# CH32V467VET-USB.net
KiCad netlist of a schematic drawn in Altium Designer
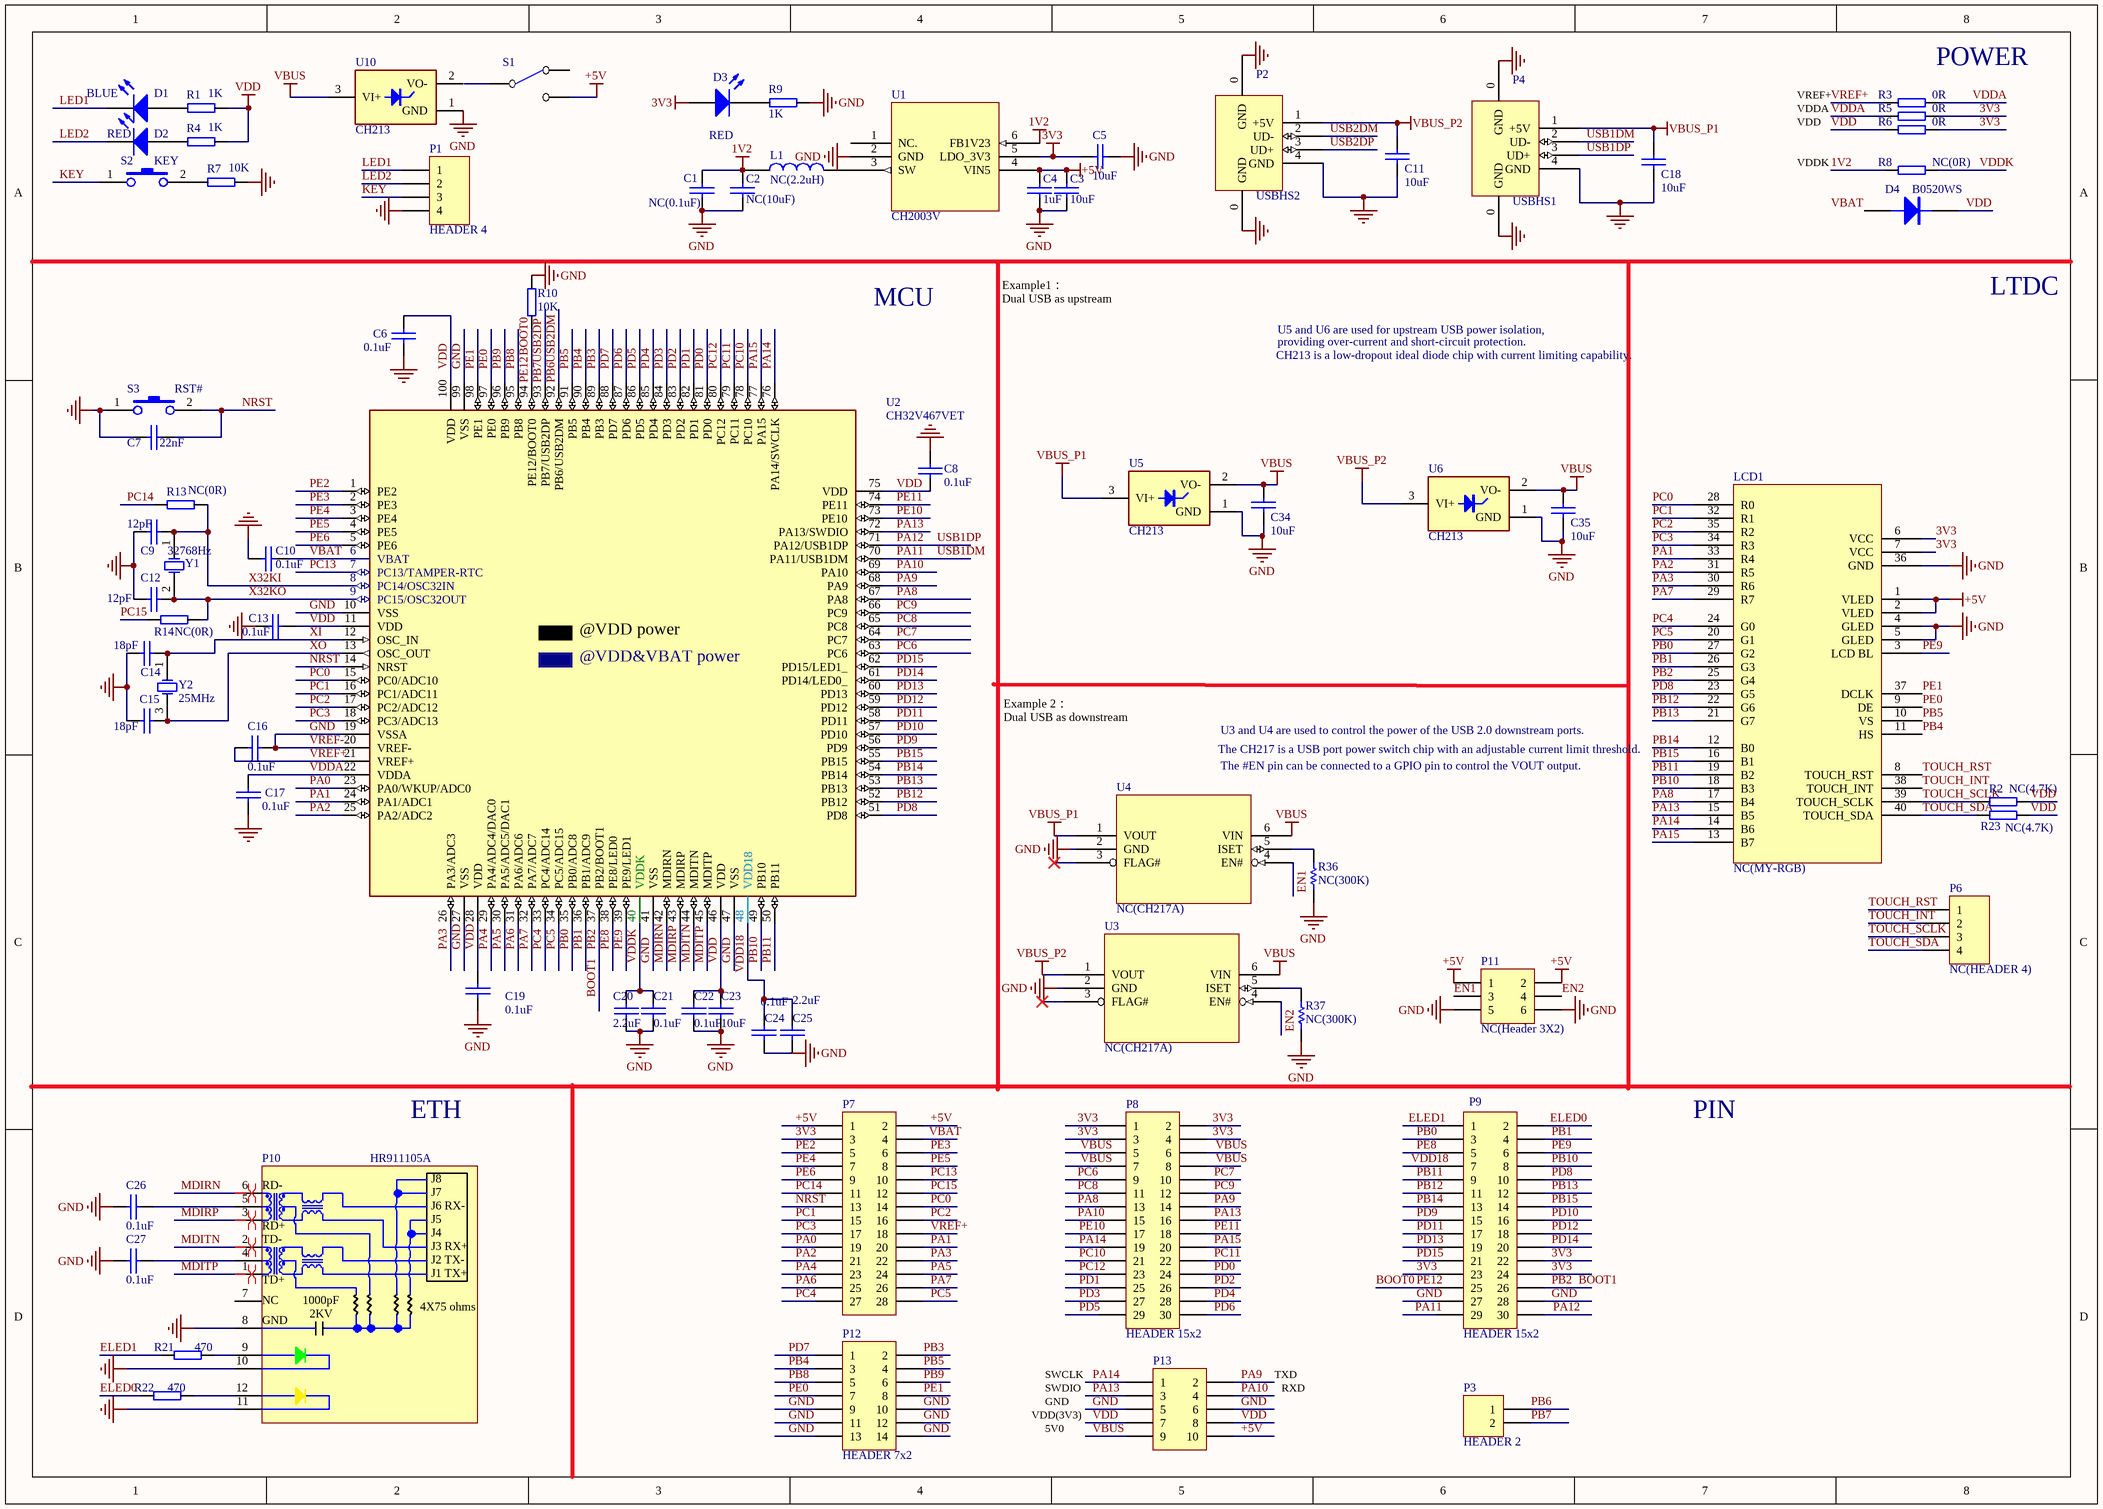
[diagram p0: CH32V467VET-USB.SchDoc]

(export (version "E")
  (design (tool "Eeschema 10.0.6"))
  (components
    (comp (ref "C1")
      (value "NC(0.1uF)")
      (footprint "0402_C")
      (description "Capacitor")
      (libsource (lib "") (part "CAP_2"))
    )
    (comp (ref "C2")
      (value "NC(10uF)")
      (footprint "0603_C")
      (description "Capacitor")
      (libsource (lib "*") (part "CAP"))
    )
    (comp (ref "C3")
      (value "10uF")
      (footprint "0603_C")
      (description "Capacitor")
      (libsource (lib "*") (part "CAP"))
    )
    (comp (ref "C4")
      (value "1uF")
      (footprint "0402_C")
      (description "Capacitor")
      (libsource (lib "") (part "CAP_2"))
    )
    (comp (ref "C5")
      (value "10uF")
      (footprint "0603_C")
      (description "Capacitor")
      (libsource (lib "*") (part "CAP"))
    )
    (comp (ref "C6")
      (value "0.1uF")
      (footprint "0402_C")
      (description "Capacitor")
      (libsource (lib "*") (part "CAP"))
    )
    (comp (ref "C7")
      (value "22nF")
      (footprint "0402_C")
      (description "Capacitor")
      (libsource (lib "") (part "CAP_1"))
    )
    (comp (ref "C8")
      (value "0.1uF")
      (footprint "0402_C")
      (description "Capacitor")
      (libsource (lib "*") (part "CAP"))
    )
    (comp (ref "C9")
      (value "12pF")
      (footprint "0402_C")
      (description "Capacitor")
      (libsource (lib "*") (part "CAP"))
    )
    (comp (ref "C10")
      (value "0.1uF")
      (footprint "0402_C")
      (description "Capacitor")
      (libsource (lib "*") (part "CAP"))
    )
    (comp (ref "C11")
      (value "10uF")
      (footprint "0603_C")
      (description "Capacitor")
      (libsource (lib "") (part "CAP_1"))
    )
    (comp (ref "C12")
      (value "12pF")
      (footprint "0402_C")
      (description "Capacitor")
      (libsource (lib "*") (part "CAP"))
    )
    (comp (ref "C13")
      (value "0.1uF")
      (footprint "0402_C")
      (description "Capacitor")
      (libsource (lib "*") (part "CAP"))
    )
    (comp (ref "C14")
      (value "18pF")
      (footprint "0402_C")
      (description "Capacitor")
      (libsource (lib "*") (part "CAP"))
    )
    (comp (ref "C15")
      (value "18pF")
      (footprint "0402_C")
      (description "Capacitor")
      (libsource (lib "*") (part "CAP"))
    )
    (comp (ref "C16")
      (value "0.1uF")
      (footprint "0402_C")
      (description "Capacitor")
      (libsource (lib "*") (part "CAP"))
    )
    (comp (ref "C17")
      (value "0.1uF")
      (footprint "0402_C")
      (description "Capacitor")
      (libsource (lib "*") (part "CAP"))
    )
    (comp (ref "C18")
      (value "10uF")
      (footprint "0603_C")
      (description "Capacitor")
      (libsource (lib "") (part "CAP_1"))
    )
    (comp (ref "C19")
      (value "0.1uF")
      (footprint "0402_C")
      (description "Capacitor")
      (libsource (lib "*") (part "CAP"))
    )
    (comp (ref "C20")
      (value "2.2uF")
      (footprint "0402_C")
      (description "Capacitor")
      (libsource (lib "*") (part "CAP"))
    )
    (comp (ref "C21")
      (value "0.1uF")
      (footprint "0402_C")
      (description "Capacitor")
      (libsource (lib "*") (part "CAP"))
    )
    (comp (ref "C22")
      (value "0.1uF")
      (footprint "0402_C")
      (description "Capacitor")
      (libsource (lib "*") (part "CAP"))
    )
    (comp (ref "C23")
      (value "10uF")
      (footprint "0402_C")
      (description "Capacitor")
      (libsource (lib "*") (part "CAP"))
    )
    (comp (ref "C24")
      (value "0.1uF")
      (footprint "0402_C")
      (description "Capacitor")
      (libsource (lib "*") (part "CAP"))
    )
    (comp (ref "C25")
      (value "2.2uF")
      (footprint "0402_C")
      (description "Capacitor")
      (libsource (lib "*") (part "CAP"))
    )
    (comp (ref "C26")
      (value "0.1uF")
      (footprint "0402_C")
      (description "Capacitor")
      (libsource (lib "wch_sch_others") (part "CAP"))
    )
    (comp (ref "C27")
      (value "0.1uF")
      (footprint "0402_C")
      (description "Capacitor")
      (libsource (lib "wch_sch_others") (part "CAP"))
    )
    (comp (ref "C34")
      (value "10uF")
      (footprint "0603_C")
      (description "Capacitor")
      (libsource (lib "") (part "CAP_1"))
    )
    (comp (ref "C35")
      (value "10uF")
      (footprint "0603_C")
      (description "Capacitor")
      (libsource (lib "") (part "CAP_1"))
    )
    (comp (ref "D1")
      (value "BLUE")
      (footprint "0603+")
      (description "Typical INFRARED GaAs LED")
      (fields (field (name "PUBLISHER") "Altium Limited"))
      (libsource (lib "*") (part "LED0"))
    )
    (comp (ref "D2")
      (value "RED")
      (footprint "0603+")
      (description "Typical INFRARED GaAs LED")
      (fields (field (name "PUBLISHER") "Altium Limited"))
      (libsource (lib "*") (part "LED0"))
    )
    (comp (ref "D3")
      (value "RED")
      (footprint "0603+")
      (description "Typical INFRARED GaAs LED")
      (fields (field (name "PUBLISHER") "Altium Limited"))
      (libsource (lib "*") (part "LED0"))
    )
    (comp (ref "D4")
      (value "B0520WS")
      (footprint "SOD-323")
      (description "Diode")
      (libsource (lib "*") (part "DIODE"))
    )
    (comp (ref "L1") (value "NC(2.2uH)") (footprint "CD32") (libsource (lib "*") (part "INDUCTOR")))
    (comp (ref "LCD1")
      (value "NC(MY-RGB)")
      (footprint "FPC40P-0.5-FK750M3")
      (libsource (lib "MY-显示") (part "MY-RGB"))
    )
    (comp (ref "P1")
      (value "HEADER 4")
      (footprint "SIP4-2.54mm")
      (description "Header, 4-Pin")
      (libsource (lib "wch_sch_others") (part "HEADER 4"))
    )
    (comp (ref "P2")
      (value "USBHS2")
      (footprint "USBAF")
      (description "USB Port")
      (libsource (lib "*") (part "USB"))
    )
    (comp (ref "P3")
      (value "HEADER 2")
      (footprint "MYPCB:SIP2-2.54mm")
      (description "Header, 2-Pin")
      (libsource (lib "wch_sch_others") (part "HEADER 2"))
    )
    (comp (ref "P4")
      (value "USBHS1")
      (footprint "USBAF")
      (description "USB Port")
      (libsource (lib "*") (part "USB"))
    )
    (comp (ref "P6")
      (value "NC(HEADER 4)")
      (footprint "SIP4-2.54mm")
      (description "Header, 4-Pin")
      (libsource (lib "wch_sch_others") (part "HEADER 4"))
    )
    (comp (ref "P7")
      (value "HEADER 14x2")
      (footprint "MYPCB:IDC28-2.54MM")
      (description "Header, 14-Pin, Dual row")
      (libsource (lib "wch_sch_others") (part "HEADER 14x2"))
    )
    (comp (ref "P8")
      (value "HEADER 15x2")
      (footprint "MYPCB:IDC30-2.54MM")
      (description "Header, 15-Pin, Dual row")
      (libsource (lib "wch_sch_others") (part "HEADER 15x2"))
    )
    (comp (ref "P9")
      (value "HEADER 15x2")
      (footprint "MYPCB:IDC30-2.54MM")
      (description "Header, 15-Pin, Dual row")
      (libsource (lib "wch_sch_others") (part "HEADER 15x2"))
    )
    (comp (ref "P10") (value "HR911105A") (footprint "HR911105A") (libsource (lib "*") (part "HR911105A")))
    (comp (ref "P11")
      (value "NC(Header 3X2)")
      (footprint "HDR2X3")
      (description "Header, 3-Pin, Dual row")
      (fields (field (name "PUBLISHER") "Altium Limited"))
      (libsource (lib "Miscellaneous Connectors") (part "Header 3X2"))
    )
    (comp (ref "P12")
      (value "HEADER 7x2")
      (footprint "MYPCB:IDC14-2.54mm")
      (description "Header, 7-Pin, Dual row")
      (libsource (lib "wch_sch_others") (part "HEADER 7x2"))
    )
    (comp (ref "P13")
      (value "LINK")
      (footprint "IDC10-2.54mm")
      (description "Header, 5-Pin, Dual row, Right Angle")
      (fields (field (name "PUBLISHER") "Altium Limited"))
      (libsource (lib "Miscellaneous Connectors") (part "Header 5X2H"))
    )
    (comp (ref "R1") (value "1K") (footprint "0402") (libsource (lib "wch_sch_others") (part "RES")))
    (comp (ref "R2") (value "NC(4.7K)") (footprint "0402") (libsource (lib "wch_sch_others") (part "RES")))
    (comp (ref "R3") (value "0R") (footprint "0402") (libsource (lib "*") (part "R")))
    (comp (ref "R4") (value "1K") (footprint "0402") (libsource (lib "wch_sch_others") (part "RES")))
    (comp (ref "R5") (value "0R") (footprint "0402") (libsource (lib "*") (part "R")))
    (comp (ref "R6") (value "0R") (footprint "0402") (libsource (lib "*") (part "R")))
    (comp (ref "R7") (value "10K") (footprint "0402") (libsource (lib "wch_sch_others") (part "RES")))
    (comp (ref "R8") (value "NC(0R)") (footprint "0402") (libsource (lib "*") (part "R")))
    (comp (ref "R9") (value "1K") (footprint "0402") (libsource (lib "wch_sch_others") (part "RES")))
    (comp (ref "R10") (value "10K") (footprint "0402") (libsource (lib "wch_sch_others") (part "RES")))
    (comp (ref "R13") (value "NC(0R)") (footprint "0402") (libsource (lib "wch_sch_others") (part "RES")))
    (comp (ref "R14") (value "NC(0R)") (footprint "0402") (libsource (lib "wch_sch_others") (part "RES")))
    (comp (ref "R21") (value "470") (footprint "0402") (libsource (lib "wch_sch_others") (part "RES")))
    (comp (ref "R22") (value "470") (footprint "0402") (libsource (lib "wch_sch_others") (part "RES")))
    (comp (ref "R23") (value "NC(4.7K)") (footprint "0402") (libsource (lib "wch_sch_others") (part "RES")))
    (comp (ref "R36")
      (value "NC(300K)")
      (footprint "0603")
      (description "Resistor")
      (fields (field (name "PUBLISHER") "Altium Limited"))
      (libsource (lib "MYLIB") (part "0603-1"))
    )
    (comp (ref "R37")
      (value "NC(300K)")
      (footprint "0603")
      (description "Resistor")
      (fields (field (name "PUBLISHER") "Altium Limited"))
      (libsource (lib "MYLIB") (part "0603-1"))
    )
    (comp (ref "S1") (value "SW SPDT") (footprint "SW1") (libsource (lib "*") (part "SW SPDT")))
    (comp (ref "S2")
      (value "KEY")
      (footprint "SMD_6.1x3.65x2.5mm-KEY")
      (libsource (lib "wch_sch_others") (part "KEY1"))
    )
    (comp (ref "S3")
      (value "RST#")
      (footprint "SMD_6.1x3.65x2.5mm-KEY")
      (libsource (lib "wch_sch_others") (part "KEY1"))
    )
    (comp (ref "U1")
      (value "CH2003V")
      (footprint "SOT-23-6")
      (description "Step-Down DC-DC Converter, 5V input, 1.23V * 800mA output, with LDO 3.3V * 200mA")
      (libsource (lib "CHXXX") (part "CH2003V"))
    )
    (comp (ref "U2")
      (value "CH32V467VET")
      (footprint "LQFP100")
      (description "RISC-V FPU HD-MCU, 175MHz, USB_480M, 100M Ethernet & Phy, CAN, DVP, ADC, DAC, SRAM")
      (libsource (lib "CHXXX") (part "CH32V467VET"))
    )
    (comp (ref "U3")
      (value "NC(CH217A)")
      (footprint "SOT-23-6")
      (description "Current-Limited USB Power Distribution Switch")
      (libsource (lib "CHXXX") (part "CH217K"))
    )
    (comp (ref "U4")
      (value "NC(CH217A)")
      (footprint "SOT-23-6")
      (description "Current-Limited USB Power Distribution Switch")
      (libsource (lib "CHXXX") (part "CH217K"))
    )
    (comp (ref "U5")
      (value "CH213")
      (footprint "SOT-23-3")
      (description "Ideal Diode 5V*1A")
      (libsource (lib "CHXXX") (part "CH213E"))
    )
    (comp (ref "U6")
      (value "CH213")
      (footprint "SOT-23-3")
      (description "Ideal Diode 5V*1A")
      (libsource (lib "CHXXX") (part "CH213E"))
    )
    (comp (ref "U10")
      (value "CH213")
      (footprint "SOT-23-3")
      (description "Ideal Diode 5V*1A")
      (libsource (lib "CHXXX") (part "CH213E"))
    )
    (comp (ref "Y1")
      (value "32768Hz")
      (footprint "FC-135")
      (description "Crystal Oscillator")
      (fields (field (name "PUBLISHER") "Altium Limited"))
      (libsource (lib "") (part "XTAL_1"))
    )
    (comp (ref "Y2")
      (value "25MHz")
      (footprint "XT3225")
      (description "Crystal Oscillator")
      (fields (field (name "PUBLISHER") "Altium Limited"))
      (libsource (lib "*") (part "XTAL"))
    )
  )
  (nets
    (net (code "1") (name "+5V") (class "Default")
      (node (ref "C3") (pin "2") (pinfunction "2_2") (pintype "passive"))
      (node (ref "C4") (pin "2") (pinfunction "2_2") (pintype "passive"))
      (node (ref "LCD1") (pin "1") (pinfunction "VLED_1") (pintype "passive"))
      (node (ref "LCD1") (pin "2") (pinfunction "VLED_2") (pintype "passive"))
      (node (ref "P11") (pin "1") (pinfunction "1_1") (pintype "passive"))
      (node (ref "P11") (pin "2") (pinfunction "2_2") (pintype "passive"))
      (node (ref "P13") (pin "10") (pinfunction "10_10") (pintype "passive"))
      (node (ref "P7") (pin "1") (pinfunction "1_1") (pintype "passive"))
      (node (ref "P7") (pin "2") (pinfunction "2_2") (pintype "passive"))
      (node (ref "S1") (pin "2") (pinfunction "NC_2") (pintype "passive"))
      (node (ref "U1") (pin "4") (pinfunction "VIN5_4") (pintype "power_in"))
    )
    (net (code "3") (name "/BOOT0") (class "Default")
      (node (ref "P9") (pin "25") (pinfunction "25_25") (pintype "passive"))
      (node (ref "R10") (pin "2") (pintype "passive"))
      (node (ref "U2") (pin "94") (pinfunction "PE12/BOOT0_94") (pintype "bidirectional"))
    )
    (net (code "4") (name "/BOOT1") (class "Default")
      (node (ref "LCD1") (pin "25") (pinfunction "G4_25") (pintype "passive"))
      (node (ref "P9") (pin "26") (pinfunction "26_26") (pintype "passive"))
      (node (ref "U2") (pin "37") (pinfunction "PB2/BOOT1_37") (pintype "bidirectional"))
    )
    (net (code "5") (name "/ELED0") (class "Default")
      (node (ref "P9") (pin "2") (pinfunction "2_2") (pintype "passive"))
      (node (ref "R22") (pin "1") (pintype "passive"))
    )
    (net (code "6") (name "/ELED1") (class "Default")
      (node (ref "P9") (pin "1") (pinfunction "1_1") (pintype "passive"))
      (node (ref "R21") (pin "1") (pintype "passive"))
    )
    (net (code "7") (name "/EN1") (class "Default")
      (node (ref "P11") (pin "3") (pinfunction "3_3") (pintype "passive"))
      (node (ref "U4") (pin "4") (pinfunction "EN#_4") (pintype "input"))
    )
    (net (code "8") (name "/EN2") (class "Default")
      (node (ref "P11") (pin "4") (pinfunction "4_4") (pintype "passive"))
      (node (ref "U3") (pin "4") (pinfunction "EN#_4") (pintype "input"))
    )
    (net (code "9") (name "/KEY") (class "Default")
      (node (ref "P1") (pin "3") (pinfunction "3_3") (pintype "passive"))
      (node (ref "S2") (pin "1") (pinfunction "1_1") (pintype "passive"))
    )
    (net (code "10") (name "/LED1") (class "Default")
      (node (ref "D1") (pin "2") (pinfunction "K_2") (pintype "passive"))
      (node (ref "P1") (pin "1") (pinfunction "1_1") (pintype "passive"))
    )
    (net (code "11") (name "/LED2") (class "Default")
      (node (ref "D2") (pin "2") (pinfunction "K_2") (pintype "passive"))
      (node (ref "P1") (pin "2") (pinfunction "2_2") (pintype "passive"))
    )
    (net (code "12") (name "/MDIRN") (class "Default")
      (node (ref "P10") (pin "6") (pintype "passive"))
      (node (ref "U2") (pin "42") (pinfunction "MDIRN_42") (pintype "bidirectional"))
    )
    (net (code "13") (name "/MDIRP") (class "Default")
      (node (ref "P10") (pin "3") (pintype "passive"))
      (node (ref "U2") (pin "43") (pinfunction "MDIRP_43") (pintype "bidirectional"))
    )
    (net (code "14") (name "/MDITN") (class "Default")
      (node (ref "P10") (pin "2") (pintype "passive"))
      (node (ref "U2") (pin "44") (pinfunction "MDITN_44") (pintype "bidirectional"))
    )
    (net (code "15") (name "/MDITP") (class "Default")
      (node (ref "P10") (pin "1") (pintype "passive"))
      (node (ref "U2") (pin "45") (pinfunction "MDITP_45") (pintype "bidirectional"))
    )
    (net (code "16") (name "/NRST") (class "Default")
      (node (ref "C7") (pin "2") (pinfunction "2_2") (pintype "passive"))
      (node (ref "P7") (pin "13") (pinfunction "13_13") (pintype "passive"))
      (node (ref "S3") (pin "2") (pinfunction "2_2") (pintype "passive"))
      (node (ref "U2") (pin "14") (pinfunction "NRST_14") (pintype "input"))
    )
    (net (code "17") (name "/PA0") (class "Default")
      (node (ref "P7") (pin "19") (pinfunction "19_19") (pintype "passive"))
      (node (ref "U2") (pin "23") (pinfunction "PA0/WKUP/ADC0_23") (pintype "bidirectional"))
    )
    (net (code "18") (name "/PA1") (class "Default")
      (node (ref "LCD1") (pin "33") (pinfunction "R4_33") (pintype "passive"))
      (node (ref "P7") (pin "20") (pinfunction "20_20") (pintype "passive"))
      (node (ref "U2") (pin "24") (pinfunction "PA1/ADC1_24") (pintype "bidirectional"))
    )
    (net (code "19") (name "/PA2") (class "Default")
      (node (ref "LCD1") (pin "31") (pinfunction "R5_31") (pintype "passive"))
      (node (ref "P7") (pin "21") (pinfunction "21_21") (pintype "passive"))
      (node (ref "U2") (pin "25") (pinfunction "PA2/ADC2_25") (pintype "bidirectional"))
    )
    (net (code "20") (name "/PA3") (class "Default")
      (node (ref "LCD1") (pin "30") (pinfunction "R6_30") (pintype "passive"))
      (node (ref "P7") (pin "22") (pinfunction "22_22") (pintype "passive"))
      (node (ref "U2") (pin "26") (pinfunction "PA3/ADC3_26") (pintype "bidirectional"))
    )
    (net (code "21") (name "/PA4") (class "Default")
      (node (ref "P7") (pin "23") (pinfunction "23_23") (pintype "passive"))
      (node (ref "U2") (pin "29") (pinfunction "PA4/ADC4/DAC0_29") (pintype "bidirectional"))
    )
    (net (code "22") (name "/PA5") (class "Default")
      (node (ref "P7") (pin "24") (pinfunction "24_24") (pintype "passive"))
      (node (ref "U2") (pin "30") (pinfunction "PA5/ADC5/DAC1_30") (pintype "bidirectional"))
    )
    (net (code "23") (name "/PA6") (class "Default")
      (node (ref "P7") (pin "25") (pinfunction "25_25") (pintype "passive"))
      (node (ref "U2") (pin "31") (pinfunction "PA6/ADC6_31") (pintype "bidirectional"))
    )
    (net (code "24") (name "/PA7") (class "Default")
      (node (ref "LCD1") (pin "29") (pinfunction "R7_29") (pintype "passive"))
      (node (ref "P7") (pin "26") (pinfunction "26_26") (pintype "passive"))
      (node (ref "U2") (pin "32") (pinfunction "PA7/ADC7_32") (pintype "bidirectional"))
    )
    (net (code "25") (name "/PA8") (class "Default")
      (node (ref "LCD1") (pin "17") (pinfunction "B4_17") (pintype "passive"))
      (node (ref "P8") (pin "13") (pinfunction "13_13") (pintype "passive"))
      (node (ref "U2") (pin "67") (pinfunction "PA8_67") (pintype "bidirectional"))
    )
    (net (code "26") (name "/PA9") (class "Default")
      (node (ref "P13") (pin "2") (pinfunction "2_2") (pintype "passive"))
      (node (ref "P8") (pin "14") (pinfunction "14_14") (pintype "passive"))
      (node (ref "U2") (pin "68") (pinfunction "PA9_68") (pintype "bidirectional"))
    )
    (net (code "27") (name "/PA10") (class "Default")
      (node (ref "P13") (pin "4") (pinfunction "4_4") (pintype "passive"))
      (node (ref "P8") (pin "15") (pinfunction "15_15") (pintype "passive"))
      (node (ref "U2") (pin "69") (pinfunction "PA10_69") (pintype "bidirectional"))
    )
    (net (code "28") (name "/PA11") (class "Default")
      (node (ref "P4") (pin "2") (pinfunction "UD-_2") (pintype "bidirectional"))
      (node (ref "P9") (pin "29") (pinfunction "29_29") (pintype "passive"))
      (node (ref "U2") (pin "70") (pinfunction "PA11/USB1DM_70") (pintype "bidirectional"))
    )
    (net (code "29") (name "/PA12") (class "Default")
      (node (ref "P4") (pin "3") (pinfunction "UD+_3") (pintype "bidirectional"))
      (node (ref "P9") (pin "30") (pinfunction "30_30") (pintype "passive"))
      (node (ref "U2") (pin "71") (pinfunction "PA12/USB1DP_71") (pintype "bidirectional"))
    )
    (net (code "30") (name "/PA13") (class "Default")
      (node (ref "LCD1") (pin "15") (pinfunction "B5_15") (pintype "passive"))
      (node (ref "P13") (pin "3") (pinfunction "3_3") (pintype "passive"))
      (node (ref "P8") (pin "16") (pinfunction "16_16") (pintype "passive"))
      (node (ref "U2") (pin "72") (pinfunction "PA13/SWDIO_72") (pintype "bidirectional"))
    )
    (net (code "31") (name "/PA14") (class "Default")
      (node (ref "LCD1") (pin "14") (pinfunction "B6_14") (pintype "passive"))
      (node (ref "P13") (pin "1") (pinfunction "1_1") (pintype "passive"))
      (node (ref "P8") (pin "19") (pinfunction "19_19") (pintype "passive"))
      (node (ref "U2") (pin "76") (pinfunction "PA14/SWCLK_76") (pintype "bidirectional"))
    )
    (net (code "32") (name "/PA15") (class "Default")
      (node (ref "LCD1") (pin "13") (pinfunction "B7_13") (pintype "passive"))
      (node (ref "P8") (pin "20") (pinfunction "20_20") (pintype "passive"))
      (node (ref "U2") (pin "77") (pinfunction "PA15_77") (pintype "bidirectional"))
    )
    (net (code "33") (name "/PB0") (class "Default")
      (node (ref "LCD1") (pin "27") (pinfunction "G2_27") (pintype "passive"))
      (node (ref "P9") (pin "3") (pinfunction "3_3") (pintype "passive"))
      (node (ref "U2") (pin "35") (pinfunction "PB0/ADC8_35") (pintype "bidirectional"))
    )
    (net (code "34") (name "/PB1") (class "Default")
      (node (ref "LCD1") (pin "26") (pinfunction "G3_26") (pintype "passive"))
      (node (ref "P9") (pin "4") (pinfunction "4_4") (pintype "passive"))
      (node (ref "U2") (pin "36") (pinfunction "PB1/ADC9_36") (pintype "bidirectional"))
    )
    (net (code "35") (name "/PB3") (class "Default")
      (node (ref "P12") (pin "2") (pinfunction "2_2") (pintype "passive"))
      (node (ref "U2") (pin "89") (pinfunction "PB3_89") (pintype "bidirectional"))
    )
    (net (code "36") (name "/PB4") (class "Default")
      (node (ref "LCD1") (pin "11") (pinfunction "HS_11") (pintype "passive"))
      (node (ref "P12") (pin "3") (pinfunction "3_3") (pintype "passive"))
      (node (ref "U2") (pin "90") (pinfunction "PB4_90") (pintype "bidirectional"))
    )
    (net (code "37") (name "/PB5") (class "Default")
      (node (ref "LCD1") (pin "10") (pinfunction "VS_10") (pintype "passive"))
      (node (ref "P12") (pin "4") (pinfunction "4_4") (pintype "passive"))
      (node (ref "U2") (pin "91") (pinfunction "PB5_91") (pintype "bidirectional"))
    )
    (net (code "38") (name "/PB6") (class "Default")
      (node (ref "P2") (pin "2") (pinfunction "UD-_2") (pintype "bidirectional"))
      (node (ref "P3") (pin "1") (pinfunction "1_1") (pintype "passive"))
      (node (ref "U2") (pin "92") (pinfunction "PB6/USB2DM_92") (pintype "bidirectional"))
    )
    (net (code "39") (name "/PB7") (class "Default")
      (node (ref "P2") (pin "3") (pinfunction "UD+_3") (pintype "bidirectional"))
      (node (ref "P3") (pin "2") (pinfunction "2_2") (pintype "passive"))
      (node (ref "U2") (pin "93") (pinfunction "PB7/USB2DP_93") (pintype "bidirectional"))
    )
    (net (code "40") (name "/PB8") (class "Default")
      (node (ref "P12") (pin "5") (pinfunction "5_5") (pintype "passive"))
      (node (ref "U2") (pin "95") (pinfunction "PB8_95") (pintype "bidirectional"))
    )
    (net (code "41") (name "/PB9") (class "Default")
      (node (ref "P12") (pin "6") (pinfunction "6_6") (pintype "passive"))
      (node (ref "U2") (pin "96") (pinfunction "PB9_96") (pintype "bidirectional"))
    )
    (net (code "42") (name "/PB10") (class "Default")
      (node (ref "LCD1") (pin "18") (pinfunction "B3_18") (pintype "passive"))
      (node (ref "P9") (pin "8") (pinfunction "8_8") (pintype "passive"))
      (node (ref "U2") (pin "49") (pinfunction "PB10_49") (pintype "bidirectional"))
    )
    (net (code "43") (name "/PB11") (class "Default")
      (node (ref "LCD1") (pin "19") (pinfunction "B2_19") (pintype "passive"))
      (node (ref "P9") (pin "9") (pinfunction "9_9") (pintype "passive"))
      (node (ref "U2") (pin "50") (pinfunction "PB11_50") (pintype "bidirectional"))
    )
    (net (code "44") (name "/PB12") (class "Default")
      (node (ref "LCD1") (pin "22") (pinfunction "G6_22") (pintype "passive"))
      (node (ref "P9") (pin "11") (pinfunction "11_11") (pintype "passive"))
      (node (ref "U2") (pin "52") (pinfunction "PB12_52") (pintype "bidirectional"))
    )
    (net (code "45") (name "/PB13") (class "Default")
      (node (ref "LCD1") (pin "21") (pinfunction "G7_21") (pintype "passive"))
      (node (ref "P9") (pin "12") (pinfunction "12_12") (pintype "passive"))
      (node (ref "U2") (pin "53") (pinfunction "PB13_53") (pintype "bidirectional"))
    )
    (net (code "46") (name "/PB14") (class "Default")
      (node (ref "LCD1") (pin "12") (pinfunction "B0_12") (pintype "passive"))
      (node (ref "P9") (pin "13") (pinfunction "13_13") (pintype "passive"))
      (node (ref "U2") (pin "54") (pinfunction "PB14_54") (pintype "bidirectional"))
    )
    (net (code "47") (name "/PB15") (class "Default")
      (node (ref "LCD1") (pin "16") (pinfunction "B1_16") (pintype "passive"))
      (node (ref "P9") (pin "14") (pinfunction "14_14") (pintype "passive"))
      (node (ref "U2") (pin "55") (pinfunction "PB15_55") (pintype "bidirectional"))
    )
    (net (code "48") (name "/PC0") (class "Default")
      (node (ref "LCD1") (pin "28") (pinfunction "R0_28") (pintype "passive"))
      (node (ref "P7") (pin "14") (pinfunction "14_14") (pintype "passive"))
      (node (ref "U2") (pin "15") (pinfunction "PC0/ADC10_15") (pintype "bidirectional"))
    )
    (net (code "49") (name "/PC1") (class "Default")
      (node (ref "LCD1") (pin "32") (pinfunction "R1_32") (pintype "passive"))
      (node (ref "P7") (pin "15") (pinfunction "15_15") (pintype "passive"))
      (node (ref "U2") (pin "16") (pinfunction "PC1/ADC11_16") (pintype "bidirectional"))
    )
    (net (code "50") (name "/PC2") (class "Default")
      (node (ref "LCD1") (pin "35") (pinfunction "R2_35") (pintype "passive"))
      (node (ref "P7") (pin "16") (pinfunction "16_16") (pintype "passive"))
      (node (ref "U2") (pin "17") (pinfunction "PC2/ADC12_17") (pintype "bidirectional"))
    )
    (net (code "51") (name "/PC3") (class "Default")
      (node (ref "LCD1") (pin "34") (pinfunction "R3_34") (pintype "passive"))
      (node (ref "P7") (pin "17") (pinfunction "17_17") (pintype "passive"))
      (node (ref "U2") (pin "18") (pinfunction "PC3/ADC13_18") (pintype "bidirectional"))
    )
    (net (code "52") (name "/PC4") (class "Default")
      (node (ref "LCD1") (pin "24") (pinfunction "G0_24") (pintype "passive"))
      (node (ref "P7") (pin "27") (pinfunction "27_27") (pintype "passive"))
      (node (ref "U2") (pin "33") (pinfunction "PC4/ADC14_33") (pintype "bidirectional"))
    )
    (net (code "53") (name "/PC5") (class "Default")
      (node (ref "LCD1") (pin "20") (pinfunction "G1_20") (pintype "passive"))
      (node (ref "P7") (pin "28") (pinfunction "28_28") (pintype "passive"))
      (node (ref "U2") (pin "34") (pinfunction "PC5/ADC15_34") (pintype "bidirectional"))
    )
    (net (code "54") (name "/PC6") (class "Default")
      (node (ref "P8") (pin "9") (pinfunction "9_9") (pintype "passive"))
      (node (ref "U2") (pin "63") (pinfunction "PC6_63") (pintype "bidirectional"))
    )
    (net (code "55") (name "/PC7") (class "Default")
      (node (ref "P8") (pin "10") (pinfunction "10_10") (pintype "passive"))
      (node (ref "U2") (pin "64") (pinfunction "PC7_64") (pintype "bidirectional"))
    )
    (net (code "56") (name "/PC8") (class "Default")
      (node (ref "P8") (pin "11") (pinfunction "11_11") (pintype "passive"))
      (node (ref "U2") (pin "65") (pinfunction "PC8_65") (pintype "bidirectional"))
    )
    (net (code "57") (name "/PC9") (class "Default")
      (node (ref "P8") (pin "12") (pinfunction "12_12") (pintype "passive"))
      (node (ref "U2") (pin "66") (pinfunction "PC9_66") (pintype "bidirectional"))
    )
    (net (code "58") (name "/PC10") (class "Default")
      (node (ref "P8") (pin "21") (pinfunction "21_21") (pintype "passive"))
      (node (ref "U2") (pin "78") (pinfunction "PC10_78") (pintype "bidirectional"))
    )
    (net (code "59") (name "/PC11") (class "Default")
      (node (ref "P8") (pin "22") (pinfunction "22_22") (pintype "passive"))
      (node (ref "U2") (pin "79") (pinfunction "PC11_79") (pintype "bidirectional"))
    )
    (net (code "60") (name "/PC12") (class "Default")
      (node (ref "P8") (pin "23") (pinfunction "23_23") (pintype "passive"))
      (node (ref "U2") (pin "80") (pinfunction "PC12_80") (pintype "bidirectional"))
    )
    (net (code "61") (name "/PC13") (class "Default")
      (node (ref "P7") (pin "10") (pinfunction "10_10") (pintype "passive"))
      (node (ref "U2") (pin "7") (pinfunction "PC13/TAMPER-RTC_7") (pintype "bidirectional"))
    )
    (net (code "62") (name "/PC14") (class "Default")
      (node (ref "P7") (pin "11") (pinfunction "11_11") (pintype "passive"))
      (node (ref "R13") (pin "1") (pintype "passive"))
    )
    (net (code "63") (name "/PC15") (class "Default")
      (node (ref "P7") (pin "12") (pinfunction "12_12") (pintype "passive"))
      (node (ref "R14") (pin "1") (pintype "passive"))
    )
    (net (code "64") (name "/PD0") (class "Default")
      (node (ref "P8") (pin "24") (pinfunction "24_24") (pintype "passive"))
      (node (ref "U2") (pin "81") (pinfunction "PD0_81") (pintype "bidirectional"))
    )
    (net (code "65") (name "/PD1") (class "Default")
      (node (ref "P8") (pin "25") (pinfunction "25_25") (pintype "passive"))
      (node (ref "U2") (pin "82") (pinfunction "PD1_82") (pintype "bidirectional"))
    )
    (net (code "66") (name "/PD2") (class "Default")
      (node (ref "P8") (pin "26") (pinfunction "26_26") (pintype "passive"))
      (node (ref "U2") (pin "83") (pinfunction "PD2_83") (pintype "bidirectional"))
    )
    (net (code "67") (name "/PD3") (class "Default")
      (node (ref "P8") (pin "27") (pinfunction "27_27") (pintype "passive"))
      (node (ref "U2") (pin "84") (pinfunction "PD3_84") (pintype "bidirectional"))
    )
    (net (code "68") (name "/PD4") (class "Default")
      (node (ref "P8") (pin "28") (pinfunction "28_28") (pintype "passive"))
      (node (ref "U2") (pin "85") (pinfunction "PD4_85") (pintype "bidirectional"))
    )
    (net (code "69") (name "/PD5") (class "Default")
      (node (ref "P8") (pin "29") (pinfunction "29_29") (pintype "passive"))
      (node (ref "U2") (pin "86") (pinfunction "PD5_86") (pintype "bidirectional"))
    )
    (net (code "70") (name "/PD6") (class "Default")
      (node (ref "P8") (pin "30") (pinfunction "30_30") (pintype "passive"))
      (node (ref "U2") (pin "87") (pinfunction "PD6_87") (pintype "bidirectional"))
    )
    (net (code "71") (name "/PD7") (class "Default")
      (node (ref "P12") (pin "1") (pinfunction "1_1") (pintype "passive"))
      (node (ref "U2") (pin "88") (pinfunction "PD7_88") (pintype "bidirectional"))
    )
    (net (code "72") (name "/PD8") (class "Default")
      (node (ref "LCD1") (pin "23") (pinfunction "G5_23") (pintype "passive"))
      (node (ref "P9") (pin "10") (pinfunction "10_10") (pintype "passive"))
      (node (ref "U2") (pin "51") (pinfunction "PD8_51") (pintype "bidirectional"))
    )
    (net (code "73") (name "/PD9") (class "Default")
      (node (ref "P9") (pin "15") (pinfunction "15_15") (pintype "passive"))
      (node (ref "U2") (pin "56") (pinfunction "PD9_56") (pintype "bidirectional"))
    )
    (net (code "74") (name "/PD10") (class "Default")
      (node (ref "P9") (pin "16") (pinfunction "16_16") (pintype "passive"))
      (node (ref "U2") (pin "57") (pinfunction "PD10_57") (pintype "bidirectional"))
    )
    (net (code "75") (name "/PD11") (class "Default")
      (node (ref "P9") (pin "17") (pinfunction "17_17") (pintype "passive"))
      (node (ref "U2") (pin "58") (pinfunction "PD11_58") (pintype "bidirectional"))
    )
    (net (code "76") (name "/PD12") (class "Default")
      (node (ref "P9") (pin "18") (pinfunction "18_18") (pintype "passive"))
      (node (ref "U2") (pin "59") (pinfunction "PD12_59") (pintype "bidirectional"))
    )
    (net (code "77") (name "/PD13") (class "Default")
      (node (ref "P9") (pin "19") (pinfunction "19_19") (pintype "passive"))
      (node (ref "U2") (pin "60") (pinfunction "PD13_60") (pintype "bidirectional"))
    )
    (net (code "78") (name "/PD14") (class "Default")
      (node (ref "P9") (pin "20") (pinfunction "20_20") (pintype "passive"))
      (node (ref "U2") (pin "61") (pinfunction "PD14/LED0__61") (pintype "bidirectional"))
    )
    (net (code "79") (name "/PD15") (class "Default")
      (node (ref "P9") (pin "21") (pinfunction "21_21") (pintype "passive"))
      (node (ref "U2") (pin "62") (pinfunction "PD15/LED1__62") (pintype "bidirectional"))
    )
    (net (code "80") (name "/PE0") (class "Default")
      (node (ref "LCD1") (pin "9") (pinfunction "DE_9") (pintype "passive"))
      (node (ref "P12") (pin "7") (pinfunction "7_7") (pintype "passive"))
      (node (ref "U2") (pin "97") (pinfunction "PE0_97") (pintype "bidirectional"))
    )
    (net (code "81") (name "/PE1") (class "Default")
      (node (ref "LCD1") (pin "37") (pinfunction "DCLK_37") (pintype "passive"))
      (node (ref "P12") (pin "8") (pinfunction "8_8") (pintype "passive"))
      (node (ref "U2") (pin "98") (pinfunction "PE1_98") (pintype "bidirectional"))
    )
    (net (code "82") (name "/PE2") (class "Default")
      (node (ref "P7") (pin "5") (pinfunction "5_5") (pintype "passive"))
      (node (ref "U2") (pin "1") (pinfunction "PE2_1") (pintype "bidirectional"))
    )
    (net (code "83") (name "/PE3") (class "Default")
      (node (ref "P7") (pin "6") (pinfunction "6_6") (pintype "passive"))
      (node (ref "U2") (pin "2") (pinfunction "PE3_2") (pintype "bidirectional"))
    )
    (net (code "84") (name "/PE4") (class "Default")
      (node (ref "P7") (pin "7") (pinfunction "7_7") (pintype "passive"))
      (node (ref "U2") (pin "3") (pinfunction "PE4_3") (pintype "bidirectional"))
    )
    (net (code "85") (name "/PE5") (class "Default")
      (node (ref "P7") (pin "8") (pinfunction "8_8") (pintype "passive"))
      (node (ref "U2") (pin "4") (pinfunction "PE5_4") (pintype "bidirectional"))
    )
    (net (code "86") (name "/PE6") (class "Default")
      (node (ref "P7") (pin "9") (pinfunction "9_9") (pintype "passive"))
      (node (ref "U2") (pin "5") (pinfunction "PE6_5") (pintype "bidirectional"))
    )
    (net (code "87") (name "/PE8") (class "Default")
      (node (ref "P9") (pin "5") (pinfunction "5_5") (pintype "passive"))
      (node (ref "U2") (pin "38") (pinfunction "PE8/LED0_38") (pintype "bidirectional"))
    )
    (net (code "88") (name "/PE9") (class "Default")
      (node (ref "LCD1") (pin "3") (pinfunction "LCD_BL_3") (pintype "passive"))
      (node (ref "P9") (pin "6") (pinfunction "6_6") (pintype "passive"))
      (node (ref "U2") (pin "39") (pinfunction "PE9/LED1_39") (pintype "bidirectional"))
    )
    (net (code "89") (name "/PE10") (class "Default")
      (node (ref "P8") (pin "17") (pinfunction "17_17") (pintype "passive"))
      (node (ref "U2") (pin "73") (pinfunction "PE10_73") (pintype "bidirectional"))
    )
    (net (code "90") (name "/PE11") (class "Default")
      (node (ref "P8") (pin "18") (pinfunction "18_18") (pintype "passive"))
      (node (ref "U2") (pin "74") (pinfunction "PE11_74") (pintype "bidirectional"))
    )
    (net (code "91") (name "/TOUCH_INT") (class "Default")
      (node (ref "LCD1") (pin "38") (pinfunction "TOUCH_INT_38") (pintype "passive"))
      (node (ref "P6") (pin "2") (pinfunction "2_2") (pintype "passive"))
    )
    (net (code "92") (name "/TOUCH_RST") (class "Default")
      (node (ref "LCD1") (pin "8") (pinfunction "TOUCH_RST_8") (pintype "passive"))
      (node (ref "P6") (pin "1") (pinfunction "1_1") (pintype "passive"))
    )
    (net (code "93") (name "/TOUCH_SCLK") (class "Default")
      (node (ref "LCD1") (pin "39") (pinfunction "TOUCH_SCLK_39") (pintype "passive"))
      (node (ref "P6") (pin "3") (pinfunction "3_3") (pintype "passive"))
      (node (ref "R2") (pin "2") (pintype "passive"))
    )
    (net (code "94") (name "/TOUCH_SDA") (class "Default")
      (node (ref "LCD1") (pin "40") (pinfunction "TOUCH_SDA_40") (pintype "passive"))
      (node (ref "P6") (pin "4") (pinfunction "4_4") (pintype "passive"))
      (node (ref "R23") (pin "2") (pintype "passive"))
    )
    (net (code "95") (name "/VBAT") (class "Default")
      (node (ref "C10") (pin "2") (pinfunction "2_2") (pintype "passive"))
      (node (ref "P7") (pin "4") (pinfunction "4_4") (pintype "passive"))
      (node (ref "U2") (pin "6") (pinfunction "VBAT_6") (pintype "power_in"))
    )
    (net (code "96") (name "/VDD18") (class "Default")
      (node (ref "C24") (pin "2") (pinfunction "2_2") (pintype "passive"))
      (node (ref "C25") (pin "2") (pinfunction "2_2") (pintype "passive"))
      (node (ref "P9") (pin "7") (pinfunction "7_7") (pintype "passive"))
      (node (ref "U2") (pin "48") (pinfunction "VDD18_48") (pintype "power_in"))
    )
    (net (code "97") (name "/VDDA") (class "Default")
      (node (ref "C17") (pin "1") (pinfunction "1_1") (pintype "passive"))
      (node (ref "R3") (pin "1") (pinfunction "1_1") (pintype "passive"))
      (node (ref "R5") (pin "2") (pinfunction "2_2") (pintype "passive"))
      (node (ref "U2") (pin "22") (pinfunction "VDDA_22") (pintype "power_in"))
    )
    (net (code "98") (name "/VDDK") (class "Default")
      (node (ref "C20") (pin "2") (pinfunction "2_2") (pintype "passive"))
      (node (ref "C21") (pin "2") (pinfunction "2_2") (pintype "passive"))
      (node (ref "R8") (pin "1") (pinfunction "1_1") (pintype "passive"))
      (node (ref "U2") (pin "40") (pinfunction "VDDK_40") (pintype "power_in"))
    )
    (net (code "99") (name "/VREF+") (class "Default")
      (node (ref "C16") (pin "1") (pinfunction "1_1") (pintype "passive"))
      (node (ref "P7") (pin "18") (pinfunction "18_18") (pintype "passive"))
      (node (ref "R3") (pin "2") (pinfunction "2_2") (pintype "passive"))
      (node (ref "U2") (pin "21") (pinfunction "VREF+_21") (pintype "power_in"))
    )
    (net (code "100") (name "/X32KI") (class "Default")
      (node (ref "C9") (pin "2") (pinfunction "2_2") (pintype "passive"))
      (node (ref "R13") (pin "2") (pintype "passive"))
      (node (ref "U2") (pin "8") (pinfunction "PC14/OSC32IN_8") (pintype "bidirectional"))
      (node (ref "Y1") (pin "1") (pinfunction "OSC1_1") (pintype "passive"))
    )
    (net (code "101") (name "/X32KO") (class "Default")
      (node (ref "C12") (pin "2") (pinfunction "2_2") (pintype "passive"))
      (node (ref "R14") (pin "2") (pintype "passive"))
      (node (ref "U2") (pin "9") (pinfunction "PC15/OSC32OUT_9") (pintype "bidirectional"))
      (node (ref "Y1") (pin "2") (pinfunction "OSC2_2") (pintype "passive"))
    )
    (net (code "102") (name "/XI") (class "Default")
      (node (ref "C14") (pin "2") (pinfunction "2_2") (pintype "passive"))
      (node (ref "U2") (pin "12") (pinfunction "OSC_IN_12") (pintype "input"))
      (node (ref "Y2") (pin "1") (pinfunction "OSC1_1") (pintype "passive"))
    )
    (net (code "103") (name "/XO") (class "Default")
      (node (ref "C15") (pin "2") (pinfunction "2_2") (pintype "passive"))
      (node (ref "U2") (pin "13") (pinfunction "OSC_OUT_13") (pintype "output"))
      (node (ref "Y2") (pin "3") (pinfunction "OSC2_3") (pintype "passive"))
    )
    (net (code "104") (name "1V2") (class "Default")
      (node (ref "C1") (pin "2") (pinfunction "2_2") (pintype "passive"))
      (node (ref "C2") (pin "2") (pinfunction "2_2") (pintype "passive"))
      (node (ref "L1") (pin "2") (pinfunction "2_2") (pintype "passive"))
      (node (ref "R8") (pin "2") (pinfunction "2_2") (pintype "passive"))
      (node (ref "U1") (pin "6") (pinfunction "FB1V23_6") (pintype "input"))
    )
    (net (code "105") (name "3V3") (class "Default")
      (node (ref "C5") (pin "2") (pinfunction "2_2") (pintype "passive"))
      (node (ref "D3") (pin "1") (pinfunction "A_1") (pintype "passive"))
      (node (ref "LCD1") (pin "6") (pinfunction "VCC_6") (pintype "passive"))
      (node (ref "LCD1") (pin "7") (pinfunction "VCC_7") (pintype "passive"))
      (node (ref "P7") (pin "3") (pinfunction "3_3") (pintype "passive"))
      (node (ref "P8") (pin "1") (pinfunction "1_1") (pintype "passive"))
      (node (ref "P8") (pin "2") (pinfunction "2_2") (pintype "passive"))
      (node (ref "P8") (pin "3") (pinfunction "3_3") (pintype "passive"))
      (node (ref "P8") (pin "4") (pinfunction "4_4") (pintype "passive"))
      (node (ref "P9") (pin "22") (pinfunction "22_22") (pintype "passive"))
      (node (ref "P9") (pin "23") (pinfunction "23_23") (pintype "passive"))
      (node (ref "P9") (pin "24") (pinfunction "24_24") (pintype "passive"))
      (node (ref "R5") (pin "1") (pinfunction "1_1") (pintype "passive"))
      (node (ref "R6") (pin "1") (pinfunction "1_1") (pintype "passive"))
      (node (ref "U1") (pin "5") (pinfunction "LDO_3V3_5") (pintype "power_in"))
    )
    (net (code "106") (name "GND") (class "Default")
      (node (ref "C1") (pin "1") (pinfunction "1_1") (pintype "passive"))
      (node (ref "C10") (pin "1") (pinfunction "1_1") (pintype "passive"))
      (node (ref "C11") (pin "2") (pinfunction "2_2") (pintype "passive"))
      (node (ref "C12") (pin "1") (pinfunction "1_1") (pintype "passive"))
      (node (ref "C13") (pin "2") (pinfunction "2_2") (pintype "passive"))
      (node (ref "C14") (pin "1") (pinfunction "1_1") (pintype "passive"))
      (node (ref "C15") (pin "1") (pinfunction "1_1") (pintype "passive"))
      (node (ref "C16") (pin "2") (pinfunction "2_2") (pintype "passive"))
      (node (ref "C17") (pin "2") (pinfunction "2_2") (pintype "passive"))
      (node (ref "C18") (pin "2") (pinfunction "2_2") (pintype "passive"))
      (node (ref "C19") (pin "1") (pinfunction "1_1") (pintype "passive"))
      (node (ref "C2") (pin "1") (pinfunction "1_1") (pintype "passive"))
      (node (ref "C20") (pin "1") (pinfunction "1_1") (pintype "passive"))
      (node (ref "C21") (pin "1") (pinfunction "1_1") (pintype "passive"))
      (node (ref "C22") (pin "1") (pinfunction "1_1") (pintype "passive"))
      (node (ref "C23") (pin "1") (pinfunction "1_1") (pintype "passive"))
      (node (ref "C25") (pin "1") (pinfunction "1_1") (pintype "passive"))
      (node (ref "C26") (pin "1") (pinfunction "1_1") (pintype "passive"))
      (node (ref "C27") (pin "1") (pinfunction "1_1") (pintype "passive"))
      (node (ref "C3") (pin "1") (pinfunction "1_1") (pintype "passive"))
      (node (ref "C34") (pin "2") (pinfunction "2_2") (pintype "passive"))
      (node (ref "C35") (pin "2") (pinfunction "2_2") (pintype "passive"))
      (node (ref "C4") (pin "1") (pinfunction "1_1") (pintype "passive"))
      (node (ref "C5") (pin "1") (pinfunction "1_1") (pintype "passive"))
      (node (ref "C6") (pin "1") (pinfunction "1_1") (pintype "passive"))
      (node (ref "C7") (pin "1") (pinfunction "1_1") (pintype "passive"))
      (node (ref "C8") (pin "2") (pinfunction "2_2") (pintype "passive"))
      (node (ref "C9") (pin "1") (pinfunction "1_1") (pintype "passive"))
      (node (ref "LCD1") (pin "36") (pinfunction "GND_36") (pintype "passive"))
      (node (ref "LCD1") (pin "4") (pinfunction "GLED_4") (pintype "passive"))
      (node (ref "LCD1") (pin "5") (pinfunction "GLED_5") (pintype "passive"))
      (node (ref "P1") (pin "4") (pinfunction "4_4") (pintype "passive"))
      (node (ref "P10") (pin "10") (pintype "passive"))
      (node (ref "P10") (pin "11") (pintype "passive"))
      (node (ref "P10") (pin "8") (pintype "passive"))
      (node (ref "P11") (pin "5") (pinfunction "5_5") (pintype "passive"))
      (node (ref "P11") (pin "6") (pinfunction "6_6") (pintype "passive"))
      (node (ref "P12") (pin "10") (pinfunction "10_10") (pintype "passive"))
      (node (ref "P12") (pin "11") (pinfunction "11_11") (pintype "passive"))
      (node (ref "P12") (pin "12") (pinfunction "12_12") (pintype "passive"))
      (node (ref "P12") (pin "13") (pinfunction "13_13") (pintype "passive"))
      (node (ref "P12") (pin "14") (pinfunction "14_14") (pintype "passive"))
      (node (ref "P12") (pin "9") (pinfunction "9_9") (pintype "passive"))
      (node (ref "P13") (pin "5") (pinfunction "5_5") (pintype "passive"))
      (node (ref "P13") (pin "6") (pinfunction "6_6") (pintype "passive"))
      (node (ref "P2") (pin "0") (pinfunction "GND_0") (pintype "power_in"))
      (node (ref "P2") (pin "4") (pinfunction "GND_4") (pintype "power_in"))
      (node (ref "P4") (pin "0") (pinfunction "GND_0") (pintype "power_in"))
      (node (ref "P4") (pin "4") (pinfunction "GND_4") (pintype "power_in"))
      (node (ref "P9") (pin "27") (pinfunction "27_27") (pintype "passive"))
      (node (ref "P9") (pin "28") (pinfunction "28_28") (pintype "passive"))
      (node (ref "R10") (pin "1") (pintype "passive"))
      (node (ref "R36") (pin "2") (pinfunction "2_2") (pintype "passive"))
      (node (ref "R37") (pin "2") (pinfunction "2_2") (pintype "passive"))
      (node (ref "R7") (pin "1") (pintype "passive"))
      (node (ref "R9") (pin "2") (pintype "passive"))
      (node (ref "S3") (pin "1") (pinfunction "1_1") (pintype "passive"))
      (node (ref "U1") (pin "2") (pinfunction "GND_2") (pintype "power_in"))
      (node (ref "U10") (pin "1") (pinfunction "GND_1") (pintype "power_in"))
      (node (ref "U2") (pin "10") (pinfunction "VSS_10") (pintype "power_in"))
      (node (ref "U2") (pin "19") (pinfunction "VSSA_19") (pintype "power_in"))
      (node (ref "U2") (pin "20") (pinfunction "VREF-_20") (pintype "power_in"))
      (node (ref "U2") (pin "27") (pinfunction "VSS_27") (pintype "power_in"))
      (node (ref "U2") (pin "41") (pinfunction "VSS_41") (pintype "power_in"))
      (node (ref "U2") (pin "47") (pinfunction "VSS_47") (pintype "power_in"))
      (node (ref "U2") (pin "99") (pinfunction "VSS_99") (pintype "power_in"))
      (node (ref "U3") (pin "2") (pinfunction "GND_2") (pintype "power_in"))
      (node (ref "U4") (pin "2") (pinfunction "GND_2") (pintype "power_in"))
      (node (ref "U5") (pin "1") (pinfunction "GND_1") (pintype "power_in"))
      (node (ref "U6") (pin "1") (pinfunction "GND_1") (pintype "power_in"))
    )
    (net (code "107") (name "Net-(C26-Pad2)") (class "Default")
      (node (ref "C26") (pin "2") (pinfunction "2_2") (pintype "passive"))
      (node (ref "P10") (pin "5") (pintype "passive"))
    )
    (net (code "108") (name "Net-(C27-Pad2)") (class "Default")
      (node (ref "C27") (pin "2") (pinfunction "2_2") (pintype "passive"))
      (node (ref "P10") (pin "4") (pintype "passive"))
    )
    (net (code "109") (name "Net-(D1-A)") (class "Default")
      (node (ref "D1") (pin "1") (pinfunction "A_1") (pintype "passive"))
      (node (ref "R1") (pin "2") (pintype "passive"))
    )
    (net (code "110") (name "Net-(D2-A)") (class "Default")
      (node (ref "D2") (pin "1") (pinfunction "A_1") (pintype "passive"))
      (node (ref "R4") (pin "2") (pintype "passive"))
    )
    (net (code "111") (name "Net-(D3-K)") (class "Default")
      (node (ref "D3") (pin "2") (pinfunction "K_2") (pintype "passive"))
      (node (ref "R9") (pin "1") (pintype "passive"))
    )
    (net (code "112") (name "Net-(P10-Pad9)") (class "Default")
      (node (ref "P10") (pin "9") (pintype "passive"))
      (node (ref "R21") (pin "2") (pintype "passive"))
    )
    (net (code "113") (name "Net-(P10-Pad12)") (class "Default")
      (node (ref "P10") (pin "12") (pintype "passive"))
      (node (ref "R22") (pin "2") (pintype "passive"))
    )
    (net (code "114") (name "Net-(R7-Pad2)") (class "Default")
      (node (ref "R7") (pin "2") (pintype "passive"))
      (node (ref "S2") (pin "2") (pinfunction "2_2") (pintype "passive"))
    )
    (net (code "115") (name "Net-(U1-SW)") (class "Default")
      (node (ref "L1") (pin "1") (pinfunction "1_1") (pintype "passive"))
      (node (ref "U1") (pin "3") (pinfunction "SW_3") (pintype "output"))
    )
    (net (code "116") (name "Net-(U3-ISET)") (class "Default")
      (node (ref "R37") (pin "1") (pinfunction "1_1") (pintype "passive"))
      (node (ref "U3") (pin "5") (pinfunction "ISET_5") (pintype "bidirectional"))
    )
    (net (code "117") (name "Net-(U4-ISET)") (class "Default")
      (node (ref "R36") (pin "1") (pinfunction "1_1") (pintype "passive"))
      (node (ref "U4") (pin "5") (pinfunction "ISET_5") (pintype "bidirectional"))
    )
    (net (code "118") (name "VBUS") (class "Default")
      (node (ref "C34") (pin "1") (pinfunction "1_1") (pintype "passive"))
      (node (ref "C35") (pin "1") (pinfunction "1_1") (pintype "passive"))
      (node (ref "P13") (pin "9") (pinfunction "9_9") (pintype "passive"))
      (node (ref "P8") (pin "5") (pinfunction "5_5") (pintype "passive"))
      (node (ref "P8") (pin "6") (pinfunction "6_6") (pintype "passive"))
      (node (ref "P8") (pin "7") (pinfunction "7_7") (pintype "passive"))
      (node (ref "P8") (pin "8") (pinfunction "8_8") (pintype "passive"))
      (node (ref "U10") (pin "3") (pinfunction "VI+_3") (pintype "power_in"))
      (node (ref "U3") (pin "6") (pinfunction "VIN_6") (pintype "power_in"))
      (node (ref "U4") (pin "6") (pinfunction "VIN_6") (pintype "power_in"))
      (node (ref "U5") (pin "2") (pinfunction "VO-_2") (pintype "power_in"))
      (node (ref "U6") (pin "2") (pinfunction "VO-_2") (pintype "power_in"))
    )
    (net (code "119") (name "VBUS_P1") (class "Default")
      (node (ref "C18") (pin "1") (pinfunction "1_1") (pintype "passive"))
      (node (ref "P4") (pin "1") (pinfunction "+5V_1") (pintype "power_in"))
      (node (ref "U4") (pin "1") (pinfunction "VOUT_1") (pintype "power_in"))
      (node (ref "U5") (pin "3") (pinfunction "VI+_3") (pintype "power_in"))
    )
    (net (code "120") (name "VBUS_P2") (class "Default")
      (node (ref "C11") (pin "1") (pinfunction "1_1") (pintype "passive"))
      (node (ref "P2") (pin "1") (pinfunction "+5V_1") (pintype "power_in"))
      (node (ref "U3") (pin "1") (pinfunction "VOUT_1") (pintype "power_in"))
      (node (ref "U6") (pin "3") (pinfunction "VI+_3") (pintype "power_in"))
    )
    (net (code "121") (name "VDD") (class "Default")
      (node (ref "C13") (pin "1") (pinfunction "1_1") (pintype "passive"))
      (node (ref "C19") (pin "2") (pinfunction "2_2") (pintype "passive"))
      (node (ref "C22") (pin "2") (pinfunction "2_2") (pintype "passive"))
      (node (ref "C23") (pin "2") (pinfunction "2_2") (pintype "passive"))
      (node (ref "C6") (pin "2") (pinfunction "2_2") (pintype "passive"))
      (node (ref "C8") (pin "1") (pinfunction "1_1") (pintype "passive"))
      (node (ref "D4") (pin "2") (pinfunction "K_2") (pintype "passive"))
      (node (ref "P13") (pin "7") (pinfunction "7_7") (pintype "passive"))
      (node (ref "P13") (pin "8") (pinfunction "8_8") (pintype "passive"))
      (node (ref "R1") (pin "1") (pintype "passive"))
      (node (ref "R2") (pin "1") (pintype "passive"))
      (node (ref "R23") (pin "1") (pintype "passive"))
      (node (ref "R4") (pin "1") (pintype "passive"))
      (node (ref "R6") (pin "2") (pinfunction "2_2") (pintype "passive"))
      (node (ref "U2") (pin "100") (pinfunction "VDD_100") (pintype "power_in"))
      (node (ref "U2") (pin "11") (pinfunction "VDD_11") (pintype "power_in"))
      (node (ref "U2") (pin "28") (pinfunction "VDD_28") (pintype "power_in"))
      (node (ref "U2") (pin "46") (pinfunction "VDD_46") (pintype "power_in"))
      (node (ref "U2") (pin "75") (pinfunction "VDD_75") (pintype "power_in"))
    )
    (net (code "122") (name "unconnected-(C24-Pad1)") (class "Default")
      (node (ref "C24") (pin "1") (pinfunction "1_1") (pintype "passive"))
    )
    (net (code "123") (name "unconnected-(D4-A-Pad1)") (class "Default")
      (node (ref "D4") (pin "1") (pinfunction "A_1") (pintype "passive"))
    )
    (net (code "124") (name "unconnected-(P10-Pad7)") (class "Default")
      (node (ref "P10") (pin "7") (pintype "passive"))
    )
    (net (code "125") (name "unconnected-(S1-COMMON-Pad1)") (class "Default")
      (node (ref "S1") (pin "1") (pinfunction "COMMON_1") (pintype "passive"))
    )
    (net (code "126") (name "unconnected-(S1-NO-Pad3)") (class "Default")
      (node (ref "S1") (pin "3") (pinfunction "NO_3") (pintype "passive"))
    )
    (net (code "127") (name "unconnected-(U1-NC.-Pad1)") (class "Default")
      (node (ref "U1") (pin "1") (pinfunction "NC._1") (pintype "passive"))
    )
    (net (code "128") (name "unconnected-(U3-FLAG#-Pad3)") (class "Default")
      (node (ref "U3") (pin "3") (pinfunction "FLAG#_3") (pintype "open_collector+no_connect"))
    )
    (net (code "129") (name "unconnected-(U4-FLAG#-Pad3)") (class "Default")
      (node (ref "U4") (pin "3") (pinfunction "FLAG#_3") (pintype "open_collector+no_connect"))
    )
    (net (code "130") (name "unconnected-(U10-VO--Pad2)") (class "Default")
      (node (ref "U10") (pin "2") (pinfunction "VO-_2") (pintype "power_in"))
    )
  )
)
